# ProPrj_6dof2_fixed.net
KiCad netlist of a schematic drawn in EasyEDA Pro
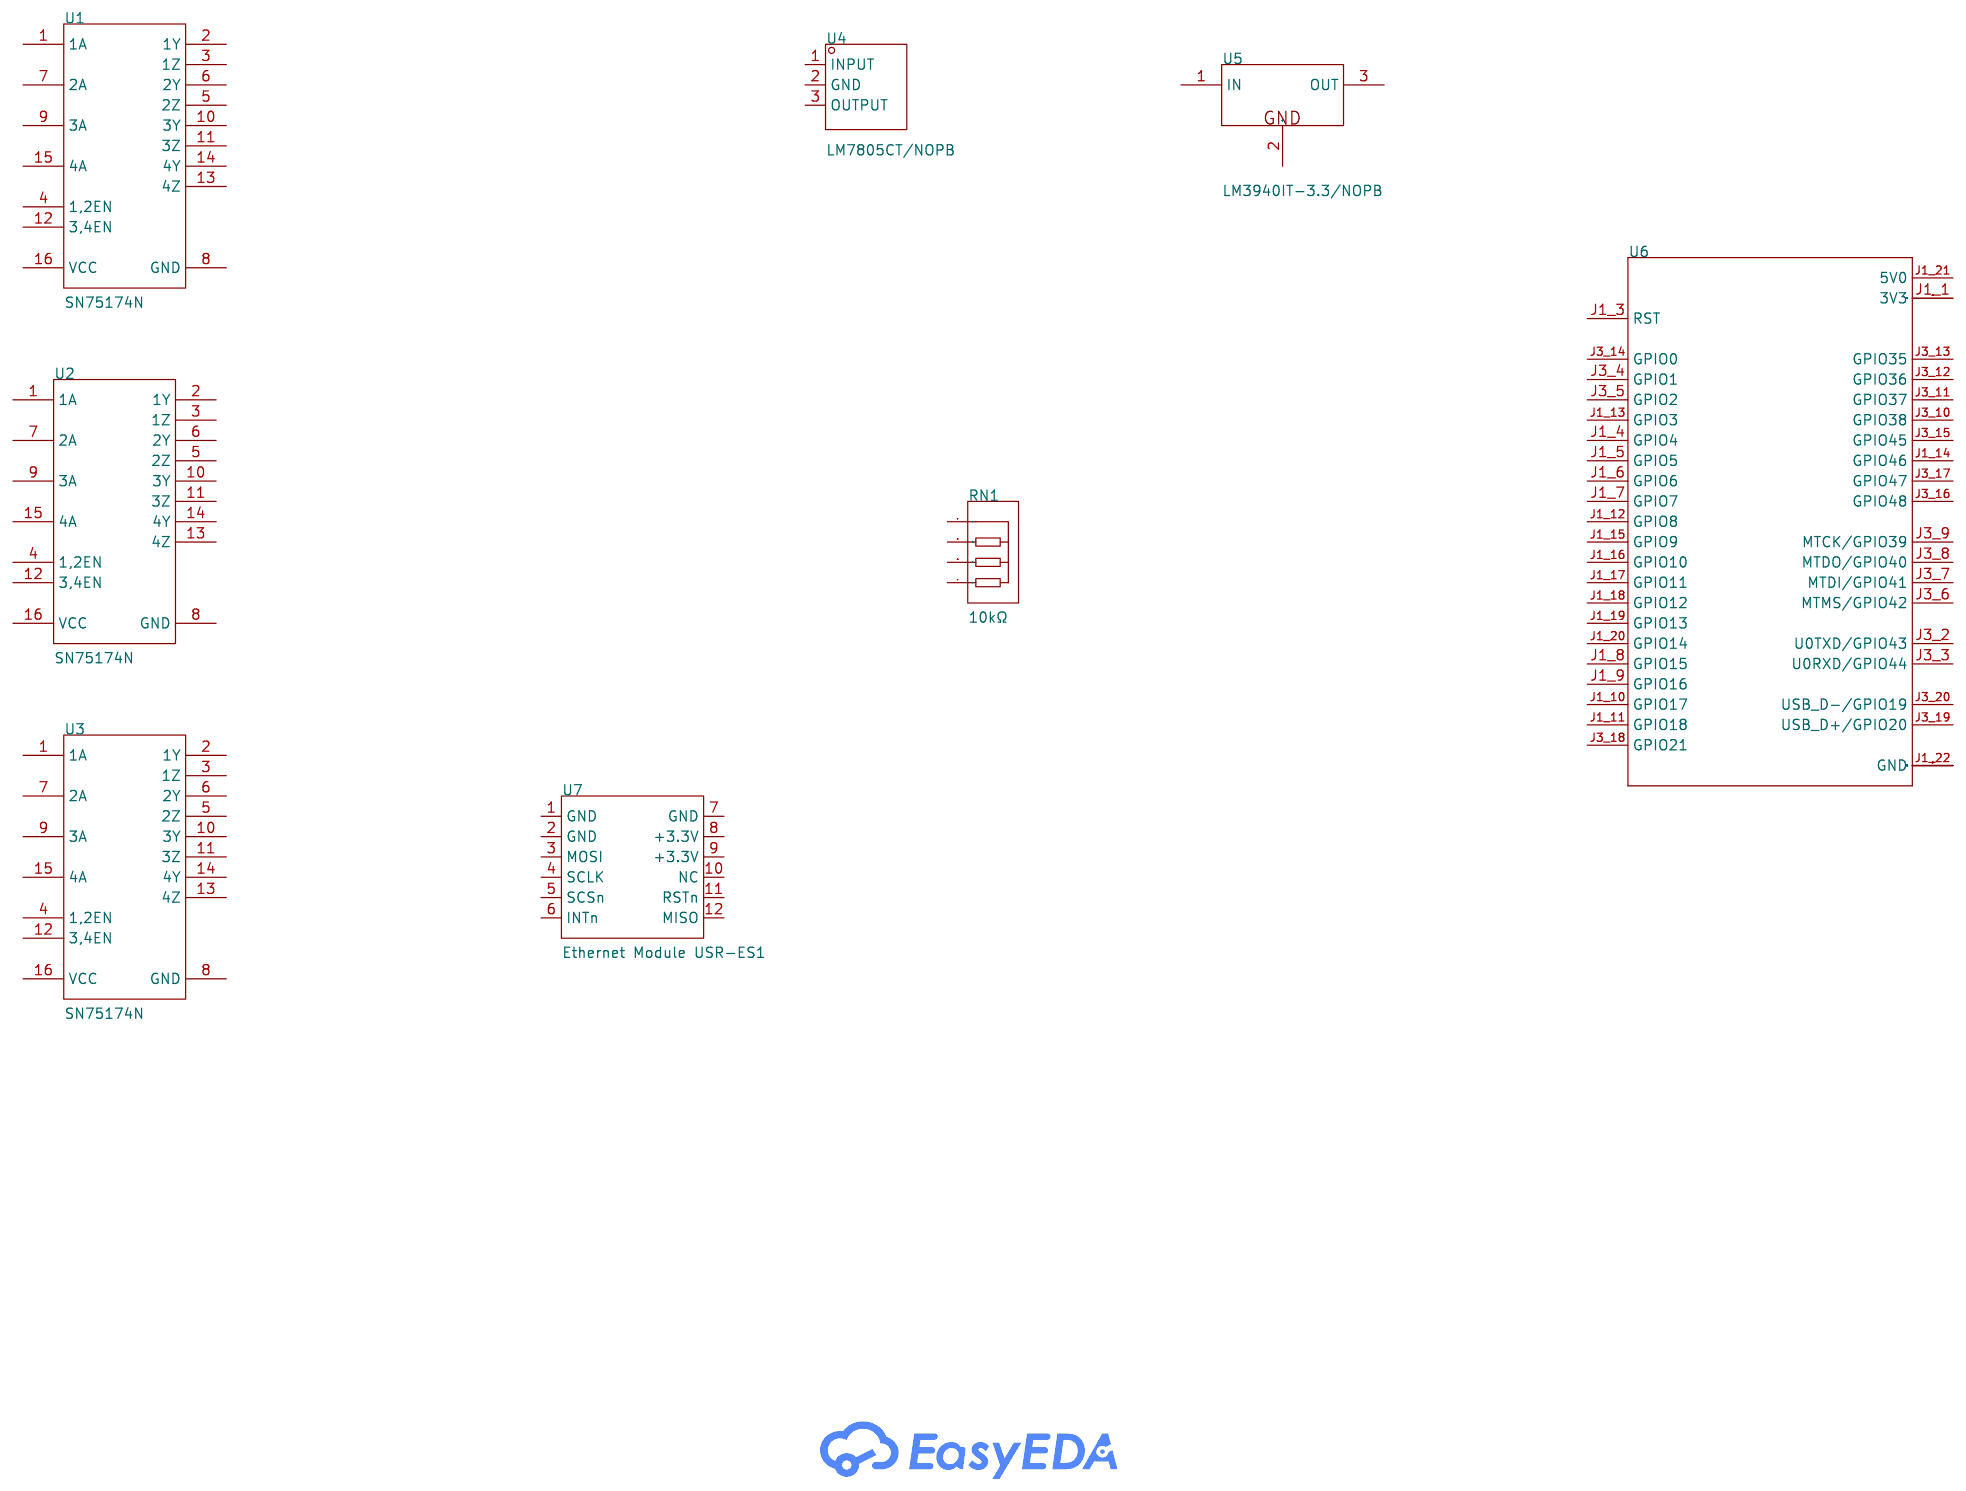
[diagram p0: schematic sheet]

(export (version "E")
  (design (tool "Eeschema 10.0.6"))
  (components
    (comp (ref "RN1")
      (value "10kΩ")
      (footprint "easyedapro:RES-ARRAY-TH_4P-P2.54-D1.0")
      (fields (field (name "Manufacturer Part") "4604X-101-103LF") (field (name "Manufacturer") "BOURNS"))
      (libsource (lib "easyedapro") (part "4604X-101-103LF"))
    )
    (comp (ref "U1")
      (value "SN75174N")
      (footprint "easyedapro:DIP-16_L20.0-W6.4-P2.54-LS7.6-BL")
      (fields (field (name "Manufacturer") "TI(德州仪器)"))
      (libsource (lib "easyedapro") (part "SN75174N"))
    )
    (comp (ref "U2")
      (value "SN75174N")
      (footprint "easyedapro:DIP-16_L20.0-W6.4-P2.54-LS7.6-BL")
      (fields (field (name "Manufacturer") "TI(德州仪器)"))
      (libsource (lib "easyedapro") (part "SN75174N"))
    )
    (comp (ref "U3")
      (value "SN75174N")
      (footprint "easyedapro:DIP-16_L20.0-W6.4-P2.54-LS7.6-BL")
      (fields (field (name "Manufacturer") "TI(德州仪器)"))
      (libsource (lib "easyedapro") (part "SN75174N"))
    )
    (comp (ref "U4")
      (value "LM7805CT/NOPB")
      (footprint "easyedapro:TO-220-3_L10.0-W4.5-P2.54-T")
      (fields (field (name "Manufacturer") "TI(德州仪器)"))
      (libsource (lib "easyedapro") (part "LM7805CT/NOPB"))
    )
    (comp (ref "U5")
      (value "LM3940IT-3.3/NOPB")
      (footprint "easyedapro:TO-220-3_L10.2-W4.6-P2.54-L")
      (fields (field (name "Manufacturer") "TI(德州仪器)"))
      (libsource (lib "easyedapro") (part "LM3940IT-3.3/NOPB"))
    )
    (comp (ref "U6")
      (value "~")
      (footprint "easyedapro:XCVR_ESP32-S3-DEVKITC-1-N8R2")
      (libsource (lib "easyedapro") (part "ESP32-S3-DEVKITC-1-N8R2"))
    )
    (comp (ref "U7")
      (value "Ethernet Module USR-ES1")
      (footprint "easyedapro:COMM_ETHERNET-MODULE-USR-ES1")
      (libsource (lib "easyedapro") (part "ETHERNET MODULE USR-ES1"))
    )
  )
  (nets
    (net (code "1") (name "Net-(U6-3V3-PadJ1_1)") (class "Default")
      (node (ref "U6") (pin "J1_1") (pinfunction "3V3_J1_1") (pintype "unspecified"))
      (node (ref "U6") (pin "J1_2") (pinfunction "3V3_J1_2") (pintype "unspecified"))
    )
    (net (code "2") (name "Net-(U6-GND-PadJ1_22)") (class "Default")
      (node (ref "U6") (pin "J1_22") (pinfunction "GND_J1_22") (pintype "unspecified"))
      (node (ref "U6") (pin "J3_1") (pinfunction "GND_J3_1") (pintype "unspecified"))
      (node (ref "U6") (pin "J3_21") (pinfunction "GND_J3_21") (pintype "unspecified"))
      (node (ref "U6") (pin "J3_22") (pinfunction "GND_J3_22") (pintype "unspecified"))
    )
    (net (code "3") (name "unconnected-(RN1-Pad1)") (class "Default")
      (node (ref "RN1") (pin "1") (pinfunction "1_1") (pintype "unspecified"))
    )
    (net (code "4") (name "unconnected-(RN1-Pad2)") (class "Default")
      (node (ref "RN1") (pin "2") (pinfunction "2_2") (pintype "unspecified"))
    )
    (net (code "5") (name "unconnected-(RN1-Pad3)") (class "Default")
      (node (ref "RN1") (pin "3") (pinfunction "3_3") (pintype "unspecified"))
    )
    (net (code "6") (name "unconnected-(RN1-Pad4)") (class "Default")
      (node (ref "RN1") (pin "4") (pinfunction "4_4") (pintype "unspecified"))
    )
    (net (code "7") (name "unconnected-(U1-1,2EN-Pad4)") (class "Default")
      (node (ref "U1") (pin "4") (pinfunction "1,2EN_4") (pintype "unspecified"))
    )
    (net (code "8") (name "unconnected-(U1-1A-Pad1)") (class "Default")
      (node (ref "U1") (pin "1") (pinfunction "1A_1") (pintype "unspecified"))
    )
    (net (code "9") (name "unconnected-(U1-1Y-Pad2)") (class "Default")
      (node (ref "U1") (pin "2") (pinfunction "1Y_2") (pintype "unspecified"))
    )
    (net (code "10") (name "unconnected-(U1-1Z-Pad3)") (class "Default")
      (node (ref "U1") (pin "3") (pinfunction "1Z_3") (pintype "unspecified"))
    )
    (net (code "11") (name "unconnected-(U1-2A-Pad7)") (class "Default")
      (node (ref "U1") (pin "7") (pinfunction "2A_7") (pintype "unspecified"))
    )
    (net (code "12") (name "unconnected-(U1-2Y-Pad6)") (class "Default")
      (node (ref "U1") (pin "6") (pinfunction "2Y_6") (pintype "unspecified"))
    )
    (net (code "13") (name "unconnected-(U1-2Z-Pad5)") (class "Default")
      (node (ref "U1") (pin "5") (pinfunction "2Z_5") (pintype "unspecified"))
    )
    (net (code "14") (name "unconnected-(U1-3,4EN-Pad12)") (class "Default")
      (node (ref "U1") (pin "12") (pinfunction "3,4EN_12") (pintype "unspecified"))
    )
    (net (code "15") (name "unconnected-(U1-3A-Pad9)") (class "Default")
      (node (ref "U1") (pin "9") (pinfunction "3A_9") (pintype "unspecified"))
    )
    (net (code "16") (name "unconnected-(U1-3Y-Pad10)") (class "Default")
      (node (ref "U1") (pin "10") (pinfunction "3Y_10") (pintype "unspecified"))
    )
    (net (code "17") (name "unconnected-(U1-3Z-Pad11)") (class "Default")
      (node (ref "U1") (pin "11") (pinfunction "3Z_11") (pintype "unspecified"))
    )
    (net (code "18") (name "unconnected-(U1-4A-Pad15)") (class "Default")
      (node (ref "U1") (pin "15") (pinfunction "4A_15") (pintype "unspecified"))
    )
    (net (code "19") (name "unconnected-(U1-4Y-Pad14)") (class "Default")
      (node (ref "U1") (pin "14") (pinfunction "4Y_14") (pintype "unspecified"))
    )
    (net (code "20") (name "unconnected-(U1-4Z-Pad13)") (class "Default")
      (node (ref "U1") (pin "13") (pinfunction "4Z_13") (pintype "unspecified"))
    )
    (net (code "21") (name "unconnected-(U1-GND-Pad8)") (class "Default")
      (node (ref "U1") (pin "8") (pinfunction "GND_8") (pintype "unspecified"))
    )
    (net (code "22") (name "unconnected-(U1-VCC-Pad16)") (class "Default")
      (node (ref "U1") (pin "16") (pinfunction "VCC_16") (pintype "unspecified"))
    )
    (net (code "23") (name "unconnected-(U2-1,2EN-Pad4)") (class "Default")
      (node (ref "U2") (pin "4") (pinfunction "1,2EN_4") (pintype "unspecified"))
    )
    (net (code "24") (name "unconnected-(U2-1A-Pad1)") (class "Default")
      (node (ref "U2") (pin "1") (pinfunction "1A_1") (pintype "unspecified"))
    )
    (net (code "25") (name "unconnected-(U2-1Y-Pad2)") (class "Default")
      (node (ref "U2") (pin "2") (pinfunction "1Y_2") (pintype "unspecified"))
    )
    (net (code "26") (name "unconnected-(U2-1Z-Pad3)") (class "Default")
      (node (ref "U2") (pin "3") (pinfunction "1Z_3") (pintype "unspecified"))
    )
    (net (code "27") (name "unconnected-(U2-2A-Pad7)") (class "Default")
      (node (ref "U2") (pin "7") (pinfunction "2A_7") (pintype "unspecified"))
    )
    (net (code "28") (name "unconnected-(U2-2Y-Pad6)") (class "Default")
      (node (ref "U2") (pin "6") (pinfunction "2Y_6") (pintype "unspecified"))
    )
    (net (code "29") (name "unconnected-(U2-2Z-Pad5)") (class "Default")
      (node (ref "U2") (pin "5") (pinfunction "2Z_5") (pintype "unspecified"))
    )
    (net (code "30") (name "unconnected-(U2-3,4EN-Pad12)") (class "Default")
      (node (ref "U2") (pin "12") (pinfunction "3,4EN_12") (pintype "unspecified"))
    )
    (net (code "31") (name "unconnected-(U2-3A-Pad9)") (class "Default")
      (node (ref "U2") (pin "9") (pinfunction "3A_9") (pintype "unspecified"))
    )
    (net (code "32") (name "unconnected-(U2-3Y-Pad10)") (class "Default")
      (node (ref "U2") (pin "10") (pinfunction "3Y_10") (pintype "unspecified"))
    )
    (net (code "33") (name "unconnected-(U2-3Z-Pad11)") (class "Default")
      (node (ref "U2") (pin "11") (pinfunction "3Z_11") (pintype "unspecified"))
    )
    (net (code "34") (name "unconnected-(U2-4A-Pad15)") (class "Default")
      (node (ref "U2") (pin "15") (pinfunction "4A_15") (pintype "unspecified"))
    )
    (net (code "35") (name "unconnected-(U2-4Y-Pad14)") (class "Default")
      (node (ref "U2") (pin "14") (pinfunction "4Y_14") (pintype "unspecified"))
    )
    (net (code "36") (name "unconnected-(U2-4Z-Pad13)") (class "Default")
      (node (ref "U2") (pin "13") (pinfunction "4Z_13") (pintype "unspecified"))
    )
    (net (code "37") (name "unconnected-(U2-GND-Pad8)") (class "Default")
      (node (ref "U2") (pin "8") (pinfunction "GND_8") (pintype "unspecified"))
    )
    (net (code "38") (name "unconnected-(U2-VCC-Pad16)") (class "Default")
      (node (ref "U2") (pin "16") (pinfunction "VCC_16") (pintype "unspecified"))
    )
    (net (code "39") (name "unconnected-(U3-1,2EN-Pad4)") (class "Default")
      (node (ref "U3") (pin "4") (pinfunction "1,2EN_4") (pintype "unspecified"))
    )
    (net (code "40") (name "unconnected-(U3-1A-Pad1)") (class "Default")
      (node (ref "U3") (pin "1") (pinfunction "1A_1") (pintype "unspecified"))
    )
    (net (code "41") (name "unconnected-(U3-1Y-Pad2)") (class "Default")
      (node (ref "U3") (pin "2") (pinfunction "1Y_2") (pintype "unspecified"))
    )
    (net (code "42") (name "unconnected-(U3-1Z-Pad3)") (class "Default")
      (node (ref "U3") (pin "3") (pinfunction "1Z_3") (pintype "unspecified"))
    )
    (net (code "43") (name "unconnected-(U3-2A-Pad7)") (class "Default")
      (node (ref "U3") (pin "7") (pinfunction "2A_7") (pintype "unspecified"))
    )
    (net (code "44") (name "unconnected-(U3-2Y-Pad6)") (class "Default")
      (node (ref "U3") (pin "6") (pinfunction "2Y_6") (pintype "unspecified"))
    )
    (net (code "45") (name "unconnected-(U3-2Z-Pad5)") (class "Default")
      (node (ref "U3") (pin "5") (pinfunction "2Z_5") (pintype "unspecified"))
    )
    (net (code "46") (name "unconnected-(U3-3,4EN-Pad12)") (class "Default")
      (node (ref "U3") (pin "12") (pinfunction "3,4EN_12") (pintype "unspecified"))
    )
    (net (code "47") (name "unconnected-(U3-3A-Pad9)") (class "Default")
      (node (ref "U3") (pin "9") (pinfunction "3A_9") (pintype "unspecified"))
    )
    (net (code "48") (name "unconnected-(U3-3Y-Pad10)") (class "Default")
      (node (ref "U3") (pin "10") (pinfunction "3Y_10") (pintype "unspecified"))
    )
    (net (code "49") (name "unconnected-(U3-3Z-Pad11)") (class "Default")
      (node (ref "U3") (pin "11") (pinfunction "3Z_11") (pintype "unspecified"))
    )
    (net (code "50") (name "unconnected-(U3-4A-Pad15)") (class "Default")
      (node (ref "U3") (pin "15") (pinfunction "4A_15") (pintype "unspecified"))
    )
    (net (code "51") (name "unconnected-(U3-4Y-Pad14)") (class "Default")
      (node (ref "U3") (pin "14") (pinfunction "4Y_14") (pintype "unspecified"))
    )
    (net (code "52") (name "unconnected-(U3-4Z-Pad13)") (class "Default")
      (node (ref "U3") (pin "13") (pinfunction "4Z_13") (pintype "unspecified"))
    )
    (net (code "53") (name "unconnected-(U3-GND-Pad8)") (class "Default")
      (node (ref "U3") (pin "8") (pinfunction "GND_8") (pintype "unspecified"))
    )
    (net (code "54") (name "unconnected-(U3-VCC-Pad16)") (class "Default")
      (node (ref "U3") (pin "16") (pinfunction "VCC_16") (pintype "unspecified"))
    )
    (net (code "55") (name "unconnected-(U4-GND-Pad2)") (class "Default")
      (node (ref "U4") (pin "2") (pinfunction "GND_2") (pintype "unspecified"))
    )
    (net (code "56") (name "unconnected-(U4-INPUT-Pad1)") (class "Default")
      (node (ref "U4") (pin "1") (pinfunction "INPUT_1") (pintype "unspecified"))
    )
    (net (code "57") (name "unconnected-(U4-OUTPUT-Pad3)") (class "Default")
      (node (ref "U4") (pin "3") (pinfunction "OUTPUT_3") (pintype "unspecified"))
    )
    (net (code "58") (name "unconnected-(U5-GND-Pad2)") (class "Default")
      (node (ref "U5") (pin "2") (pinfunction "GND_2") (pintype "unspecified"))
    )
    (net (code "59") (name "unconnected-(U5-IN-Pad1)") (class "Default")
      (node (ref "U5") (pin "1") (pinfunction "IN_1") (pintype "unspecified"))
    )
    (net (code "60") (name "unconnected-(U5-OUT-Pad3)") (class "Default")
      (node (ref "U5") (pin "3") (pinfunction "OUT_3") (pintype "unspecified"))
    )
    (net (code "61") (name "unconnected-(U6-5V0-PadJ1_21)") (class "Default")
      (node (ref "U6") (pin "J1_21") (pinfunction "5V0_J1_21") (pintype "unspecified"))
    )
    (net (code "62") (name "unconnected-(U6-GPIO0-PadJ3_14)") (class "Default")
      (node (ref "U6") (pin "J3_14") (pinfunction "GPIO0_J3_14") (pintype "bidirectional"))
    )
    (net (code "63") (name "unconnected-(U6-GPIO1-PadJ3_4)") (class "Default")
      (node (ref "U6") (pin "J3_4") (pinfunction "GPIO1_J3_4") (pintype "bidirectional"))
    )
    (net (code "64") (name "unconnected-(U6-GPIO2-PadJ3_5)") (class "Default")
      (node (ref "U6") (pin "J3_5") (pinfunction "GPIO2_J3_5") (pintype "bidirectional"))
    )
    (net (code "65") (name "unconnected-(U6-GPIO3-PadJ1_13)") (class "Default")
      (node (ref "U6") (pin "J1_13") (pinfunction "GPIO3_J1_13") (pintype "bidirectional"))
    )
    (net (code "66") (name "unconnected-(U6-GPIO4-PadJ1_4)") (class "Default")
      (node (ref "U6") (pin "J1_4") (pinfunction "GPIO4_J1_4") (pintype "bidirectional"))
    )
    (net (code "67") (name "unconnected-(U6-GPIO5-PadJ1_5)") (class "Default")
      (node (ref "U6") (pin "J1_5") (pinfunction "GPIO5_J1_5") (pintype "bidirectional"))
    )
    (net (code "68") (name "unconnected-(U6-GPIO6-PadJ1_6)") (class "Default")
      (node (ref "U6") (pin "J1_6") (pinfunction "GPIO6_J1_6") (pintype "bidirectional"))
    )
    (net (code "69") (name "unconnected-(U6-GPIO7-PadJ1_7)") (class "Default")
      (node (ref "U6") (pin "J1_7") (pinfunction "GPIO7_J1_7") (pintype "bidirectional"))
    )
    (net (code "70") (name "unconnected-(U6-GPIO8-PadJ1_12)") (class "Default")
      (node (ref "U6") (pin "J1_12") (pinfunction "GPIO8_J1_12") (pintype "bidirectional"))
    )
    (net (code "71") (name "unconnected-(U6-GPIO9-PadJ1_15)") (class "Default")
      (node (ref "U6") (pin "J1_15") (pinfunction "GPIO9_J1_15") (pintype "bidirectional"))
    )
    (net (code "72") (name "unconnected-(U6-GPIO10-PadJ1_16)") (class "Default")
      (node (ref "U6") (pin "J1_16") (pinfunction "GPIO10_J1_16") (pintype "bidirectional"))
    )
    (net (code "73") (name "unconnected-(U6-GPIO11-PadJ1_17)") (class "Default")
      (node (ref "U6") (pin "J1_17") (pinfunction "GPIO11_J1_17") (pintype "bidirectional"))
    )
    (net (code "74") (name "unconnected-(U6-GPIO12-PadJ1_18)") (class "Default")
      (node (ref "U6") (pin "J1_18") (pinfunction "GPIO12_J1_18") (pintype "bidirectional"))
    )
    (net (code "75") (name "unconnected-(U6-GPIO13-PadJ1_19)") (class "Default")
      (node (ref "U6") (pin "J1_19") (pinfunction "GPIO13_J1_19") (pintype "bidirectional"))
    )
    (net (code "76") (name "unconnected-(U6-GPIO14-PadJ1_20)") (class "Default")
      (node (ref "U6") (pin "J1_20") (pinfunction "GPIO14_J1_20") (pintype "bidirectional"))
    )
    (net (code "77") (name "unconnected-(U6-GPIO15-PadJ1_8)") (class "Default")
      (node (ref "U6") (pin "J1_8") (pinfunction "GPIO15_J1_8") (pintype "bidirectional"))
    )
    (net (code "78") (name "unconnected-(U6-GPIO16-PadJ1_9)") (class "Default")
      (node (ref "U6") (pin "J1_9") (pinfunction "GPIO16_J1_9") (pintype "bidirectional"))
    )
    (net (code "79") (name "unconnected-(U6-GPIO17-PadJ1_10)") (class "Default")
      (node (ref "U6") (pin "J1_10") (pinfunction "GPIO17_J1_10") (pintype "bidirectional"))
    )
    (net (code "80") (name "unconnected-(U6-GPIO18-PadJ1_11)") (class "Default")
      (node (ref "U6") (pin "J1_11") (pinfunction "GPIO18_J1_11") (pintype "bidirectional"))
    )
    (net (code "81") (name "unconnected-(U6-GPIO21-PadJ3_18)") (class "Default")
      (node (ref "U6") (pin "J3_18") (pinfunction "GPIO21_J3_18") (pintype "bidirectional"))
    )
    (net (code "82") (name "unconnected-(U6-GPIO35-PadJ3_13)") (class "Default")
      (node (ref "U6") (pin "J3_13") (pinfunction "GPIO35_J3_13") (pintype "bidirectional"))
    )
    (net (code "83") (name "unconnected-(U6-GPIO36-PadJ3_12)") (class "Default")
      (node (ref "U6") (pin "J3_12") (pinfunction "GPIO36_J3_12") (pintype "bidirectional"))
    )
    (net (code "84") (name "unconnected-(U6-GPIO37-PadJ3_11)") (class "Default")
      (node (ref "U6") (pin "J3_11") (pinfunction "GPIO37_J3_11") (pintype "bidirectional"))
    )
    (net (code "85") (name "unconnected-(U6-GPIO38-PadJ3_10)") (class "Default")
      (node (ref "U6") (pin "J3_10") (pinfunction "GPIO38_J3_10") (pintype "bidirectional"))
    )
    (net (code "86") (name "unconnected-(U6-GPIO45-PadJ3_15)") (class "Default")
      (node (ref "U6") (pin "J3_15") (pinfunction "GPIO45_J3_15") (pintype "bidirectional"))
    )
    (net (code "87") (name "unconnected-(U6-GPIO46-PadJ1_14)") (class "Default")
      (node (ref "U6") (pin "J1_14") (pinfunction "GPIO46_J1_14") (pintype "bidirectional"))
    )
    (net (code "88") (name "unconnected-(U6-GPIO47-PadJ3_17)") (class "Default")
      (node (ref "U6") (pin "J3_17") (pinfunction "GPIO47_J3_17") (pintype "bidirectional"))
    )
    (net (code "89") (name "unconnected-(U6-GPIO48-PadJ3_16)") (class "Default")
      (node (ref "U6") (pin "J3_16") (pinfunction "GPIO48_J3_16") (pintype "bidirectional"))
    )
    (net (code "90") (name "unconnected-(U6-MTCK{slash}GPIO39-PadJ3_9)") (class "Default")
      (node (ref "U6") (pin "J3_9") (pinfunction "MTCK/GPIO39_J3_9") (pintype "bidirectional"))
    )
    (net (code "91") (name "unconnected-(U6-MTDI{slash}GPIO41-PadJ3_7)") (class "Default")
      (node (ref "U6") (pin "J3_7") (pinfunction "MTDI/GPIO41_J3_7") (pintype "bidirectional"))
    )
    (net (code "92") (name "unconnected-(U6-MTDO{slash}GPIO40-PadJ3_8)") (class "Default")
      (node (ref "U6") (pin "J3_8") (pinfunction "MTDO/GPIO40_J3_8") (pintype "bidirectional"))
    )
    (net (code "93") (name "unconnected-(U6-MTMS{slash}GPIO42-PadJ3_6)") (class "Default")
      (node (ref "U6") (pin "J3_6") (pinfunction "MTMS/GPIO42_J3_6") (pintype "bidirectional"))
    )
    (net (code "94") (name "unconnected-(U6-RST-PadJ1_3)") (class "Default")
      (node (ref "U6") (pin "J1_3") (pinfunction "RST_J1_3") (pintype "input"))
    )
    (net (code "95") (name "unconnected-(U6-U0RXD{slash}GPIO44-PadJ3_3)") (class "Default")
      (node (ref "U6") (pin "J3_3") (pinfunction "U0RXD/GPIO44_J3_3") (pintype "bidirectional"))
    )
    (net (code "96") (name "unconnected-(U6-U0TXD{slash}GPIO43-PadJ3_2)") (class "Default")
      (node (ref "U6") (pin "J3_2") (pinfunction "U0TXD/GPIO43_J3_2") (pintype "bidirectional"))
    )
    (net (code "97") (name "unconnected-(U6-USB_D+{slash}GPIO20-PadJ3_19)") (class "Default")
      (node (ref "U6") (pin "J3_19") (pinfunction "USB_D+/GPIO20_J3_19") (pintype "bidirectional"))
    )
    (net (code "98") (name "unconnected-(U6-USB_D-{slash}GPIO19-PadJ3_20)") (class "Default")
      (node (ref "U6") (pin "J3_20") (pinfunction "USB_D-/GPIO19_J3_20") (pintype "bidirectional"))
    )
    (net (code "99") (name "unconnected-(U7-+3.3V-Pad8)") (class "Default")
      (node (ref "U7") (pin "8") (pinfunction "+3.3V_8") (pintype "unspecified"))
    )
    (net (code "100") (name "unconnected-(U7-+3.3V-Pad9)") (class "Default")
      (node (ref "U7") (pin "9") (pinfunction "+3.3V_9") (pintype "unspecified"))
    )
    (net (code "101") (name "unconnected-(U7-GND-Pad1)") (class "Default")
      (node (ref "U7") (pin "1") (pinfunction "GND_1") (pintype "unspecified"))
    )
    (net (code "102") (name "unconnected-(U7-GND-Pad2)") (class "Default")
      (node (ref "U7") (pin "2") (pinfunction "GND_2") (pintype "unspecified"))
    )
    (net (code "103") (name "unconnected-(U7-GND-Pad7)") (class "Default")
      (node (ref "U7") (pin "7") (pinfunction "GND_7") (pintype "unspecified"))
    )
    (net (code "104") (name "unconnected-(U7-INTn-Pad6)") (class "Default")
      (node (ref "U7") (pin "6") (pinfunction "INTn_6") (pintype "unspecified"))
    )
    (net (code "105") (name "unconnected-(U7-MISO-Pad12)") (class "Default")
      (node (ref "U7") (pin "12") (pinfunction "MISO_12") (pintype "unspecified"))
    )
    (net (code "106") (name "unconnected-(U7-MOSI-Pad3)") (class "Default")
      (node (ref "U7") (pin "3") (pinfunction "MOSI_3") (pintype "unspecified"))
    )
    (net (code "107") (name "unconnected-(U7-NC-Pad10)") (class "Default")
      (node (ref "U7") (pin "10") (pinfunction "NC_10") (pintype "unspecified"))
    )
    (net (code "108") (name "unconnected-(U7-RSTn-Pad11)") (class "Default")
      (node (ref "U7") (pin "11") (pinfunction "RSTn_11") (pintype "unspecified"))
    )
    (net (code "109") (name "unconnected-(U7-SCLK-Pad4)") (class "Default")
      (node (ref "U7") (pin "4") (pinfunction "SCLK_4") (pintype "unspecified"))
    )
    (net (code "110") (name "unconnected-(U7-SCSn-Pad5)") (class "Default")
      (node (ref "U7") (pin "5") (pinfunction "SCSn_5") (pintype "unspecified"))
    )
  )
)
